# UNO-TH_Rev3e_Eagle.net
KiCad netlist of a schematic drawn in EAGLE
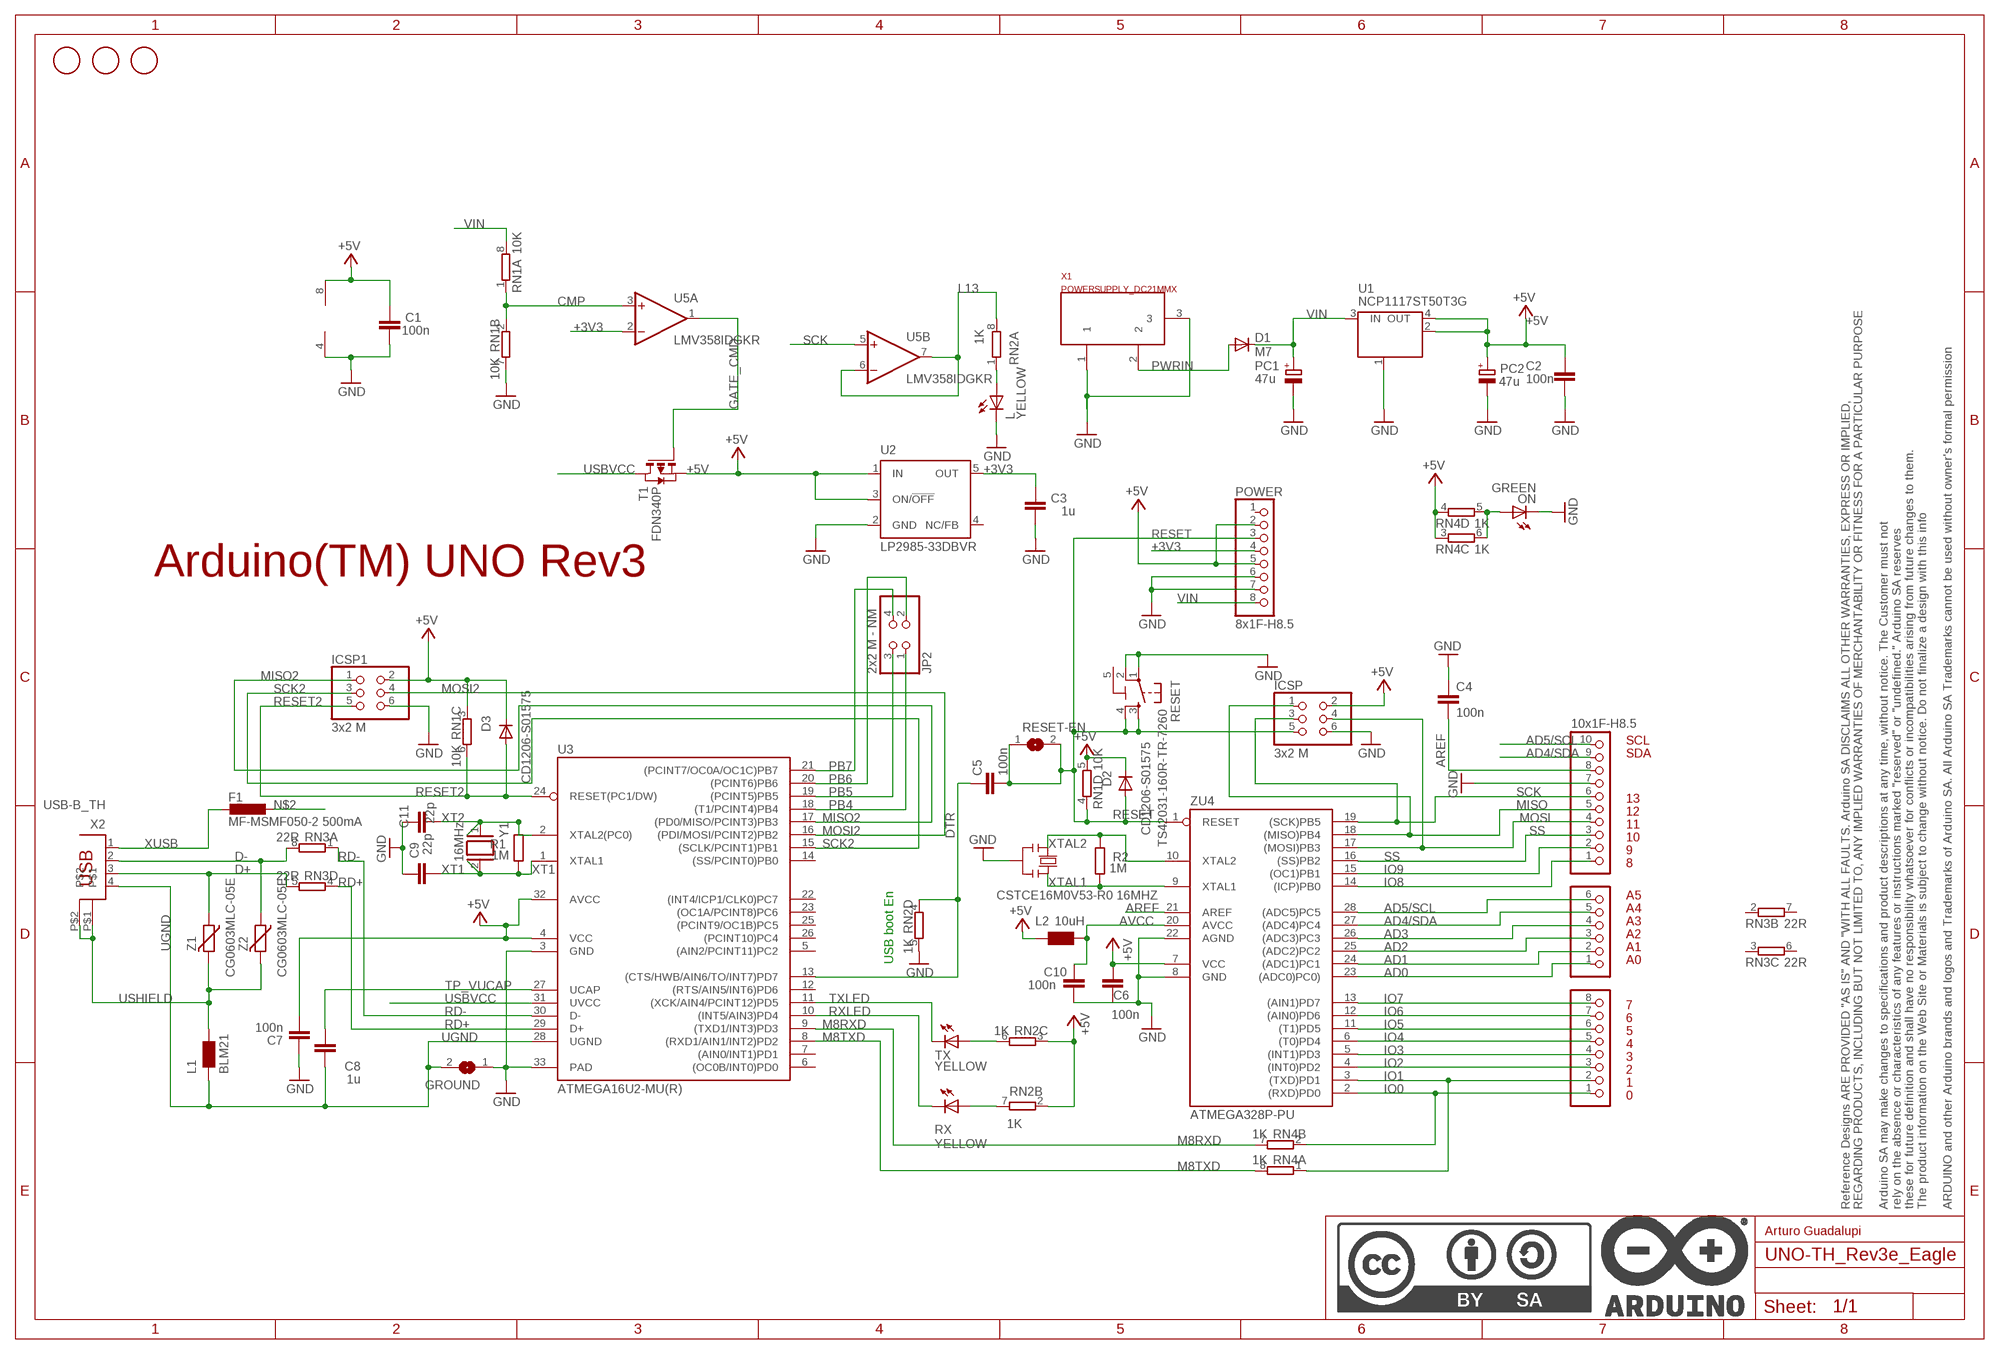
[diagram p0: schematic, sheet 1]

(export (version "E")
  (design (tool "Eeschema 10.0.6"))
  (components
    (comp (ref "AD")
      (value "6x1F-H8.5")
      (footprint "eagle-import:1X06")
      (libsource (lib "eagle-import") (part "PINHD-1X6"))
    )
    (comp (ref "C1")
      (value "100n")
      (footprint "eagle-import:C0603-ROUND")
      (libsource (lib "eagle-import") (part "C-EU0603-RND"))
    )
    (comp (ref "C2")
      (value "100n")
      (footprint "eagle-import:C0603-ROUND")
      (libsource (lib "eagle-import") (part "C-EU0603-RND"))
    )
    (comp (ref "C3")
      (value "1u")
      (footprint "eagle-import:C0603-ROUND")
      (libsource (lib "eagle-import") (part "C-EU0603-RND"))
    )
    (comp (ref "C4")
      (value "100n")
      (footprint "eagle-import:C0603-ROUND")
      (libsource (lib "eagle-import") (part "C-EU0603-RND"))
    )
    (comp (ref "C5")
      (value "100n")
      (footprint "eagle-import:C0603-ROUND")
      (libsource (lib "eagle-import") (part "C-EU0603-RND"))
    )
    (comp (ref "C6")
      (value "100n")
      (footprint "eagle-import:C0603-ROUND")
      (libsource (lib "eagle-import") (part "C-EU0603-RND"))
    )
    (comp (ref "C7")
      (value "100n")
      (footprint "eagle-import:C0603-ROUND")
      (libsource (lib "eagle-import") (part "C-EU0603-RND"))
    )
    (comp (ref "C8")
      (value "1u")
      (footprint "eagle-import:C0603-ROUND")
      (libsource (lib "eagle-import") (part "C-EU0603-RND"))
    )
    (comp (ref "C9")
      (value "22p")
      (footprint "eagle-import:C0603-ROUND")
      (libsource (lib "eagle-import") (part "C-EU0603-RND"))
    )
    (comp (ref "C10")
      (value "100n")
      (footprint "eagle-import:C0603-ROUND")
      (libsource (lib "eagle-import") (part "C-EU0603-RND"))
    )
    (comp (ref "C11")
      (value "22p")
      (footprint "eagle-import:C0603-ROUND")
      (libsource (lib "eagle-import") (part "C-EU0603-RND"))
    )
    (comp (ref "D1")
      (value "M7")
      (footprint "eagle-import:SMB")
      (libsource (lib "eagle-import") (part "DIODE-SMB"))
    )
    (comp (ref "D2")
      (value "CD1206-S01575")
      (footprint "eagle-import:MINIMELF")
      (libsource (lib "eagle-import") (part "DIODE-MINIMELF"))
    )
    (comp (ref "D3")
      (value "CD1206-S01575")
      (footprint "eagle-import:MINIMELF")
      (libsource (lib "eagle-import") (part "DIODE-MINIMELF"))
    )
    (comp (ref "F1")
      (value "MF-MSMF050-2 500mA")
      (footprint "eagle-import:L1812")
      (libsource (lib "eagle-import") (part "L-EUL1812"))
    )
    (comp (ref "FD1")
      (value "FIDUCIALMOUNT")
      (footprint "eagle-import:FIDUCIA-MOUNT")
      (libsource (lib "eagle-import") (part "FIDUCIALMOUNT"))
    )
    (comp (ref "FD2")
      (value "FIDUCIALMOUNT")
      (footprint "eagle-import:FIDUCIA-MOUNT")
      (libsource (lib "eagle-import") (part "FIDUCIALMOUNT"))
    )
    (comp (ref "FD3")
      (value "FIDUCIALMOUNT")
      (footprint "eagle-import:FIDUCIA-MOUNT")
      (libsource (lib "eagle-import") (part "FIDUCIALMOUNT"))
    )
    (comp (ref "FRAME1")
      (value "DNP")
      (footprint "eagle-import:FRAME")
      (libsource (lib "eagle-import") (part "A3-FRAME"))
    )
    (comp (ref "GROUND")
      (value "SJ")
      (footprint "eagle-import:SJ")
      (libsource (lib "eagle-import") (part "SJ"))
    )
    (comp (ref "ICSP")
      (value "3x2 M")
      (footprint "eagle-import:2X03")
      (libsource (lib "eagle-import") (part "PINHD-2X3"))
    )
    (comp (ref "ICSP1")
      (value "3x2 M")
      (footprint "eagle-import:2X03")
      (libsource (lib "eagle-import") (part "PINHD-2X3"))
    )
    (comp (ref "IOH")
      (value "10x1F-H8.5")
      (footprint "eagle-import:1X10")
      (libsource (lib "eagle-import") (part "PINHD-1X10_ARD"))
    )
    (comp (ref "IOL")
      (value "8x1F-H8.5")
      (footprint "eagle-import:1X08")
      (libsource (lib "eagle-import") (part "PINHD-1X8"))
    )
    (comp (ref "JP2")
      (value "2x2 M - NM")
      (footprint "eagle-import:2X02")
      (libsource (lib "eagle-import") (part "PINHD-2X2"))
    )
    (comp (ref "L")
      (value "YELLOW")
      (footprint "eagle-import:CHIP-LED0805")
      (libsource (lib "eagle-import") (part "LEDCHIP-LED0805"))
    )
    (comp (ref "L1")
      (value "BLM21")
      (footprint "eagle-import:0805")
      (libsource (lib "eagle-import") (part "WE-CBF_0805"))
    )
    (comp (ref "L2")
      (value "10uH")
      (footprint "eagle-import:0805")
      (fields (field (name "PART_NUMBER") "CV201210-100K"))
      (libsource (lib "eagle-import") (part "0715_CV201210-100K"))
    )
    (comp (ref "ON")
      (value "GREEN")
      (footprint "eagle-import:CHIP-LED0805")
      (libsource (lib "eagle-import") (part "LEDCHIP-LED0805"))
    )
    (comp (ref "PC1")
      (value "47u")
      (footprint "eagle-import:PANASONIC_D")
      (libsource (lib "eagle-import") (part "CPOL-EUD"))
    )
    (comp (ref "PC2")
      (value "47u")
      (footprint "eagle-import:PANASONIC_D")
      (libsource (lib "eagle-import") (part "CPOL-EUD"))
    )
    (comp (ref "POWER")
      (value "8x1F-H8.5")
      (footprint "eagle-import:1X08")
      (libsource (lib "eagle-import") (part "PINHD-1X8"))
    )
    (comp (ref "R1")
      (value "1M")
      (footprint "eagle-import:R0603-ROUND")
      (libsource (lib "eagle-import") (part "R-EU_R0603"))
    )
    (comp (ref "R2")
      (value "1M")
      (footprint "eagle-import:R0603-ROUND")
      (libsource (lib "eagle-import") (part "R-EU_R0603"))
    )
    (comp (ref "RESET")
      (value "TS42031-160R-TR-7260")
      (footprint "eagle-import:TS42")
      (libsource (lib "eagle-import") (part "TS42"))
    )
    (comp (ref "RESET-EN")
      (value "SJ")
      (footprint "eagle-import:SJ")
      (libsource (lib "eagle-import") (part "SJ"))
    )
    (comp (ref "RN1")
      (value "10K")
      (footprint "eagle-import:CAY16")
      (libsource (lib "eagle-import") (part "4R-NCAY16"))
    )
    (comp (ref "RN2")
      (value "1K")
      (footprint "eagle-import:CAY16")
      (libsource (lib "eagle-import") (part "4R-NCAY16"))
    )
    (comp (ref "RN3")
      (value "22R")
      (footprint "eagle-import:CAY16")
      (libsource (lib "eagle-import") (part "4R-NCAY16"))
    )
    (comp (ref "RN4")
      (value "1K")
      (footprint "eagle-import:CAY16")
      (libsource (lib "eagle-import") (part "4R-NCAY16"))
    )
    (comp (ref "RX")
      (value "YELLOW")
      (footprint "eagle-import:CHIP-LED0805")
      (libsource (lib "eagle-import") (part "LEDCHIP-LED0805"))
    )
    (comp (ref "T1")
      (value "FDN340P")
      (footprint "eagle-import:SOT-23")
      (libsource (lib "eagle-import") (part "PMOSSOT23"))
    )
    (comp (ref "TX")
      (value "YELLOW")
      (footprint "eagle-import:CHIP-LED0805")
      (libsource (lib "eagle-import") (part "LEDCHIP-LED0805"))
    )
    (comp (ref "U1")
      (value "NCP1117ST50T3G")
      (footprint "eagle-import:SOT223")
      (libsource (lib "eagle-import") (part "MC33269ST-3.3T3"))
    )
    (comp (ref "U2")
      (value "LP2985-33DBVR")
      (footprint "eagle-import:SOT23-DBV")
      (libsource (lib "eagle-import") (part "LP2985-XXDBVR33"))
    )
    (comp (ref "U3")
      (value "ATMEGA16U2-MU(R)")
      (footprint "eagle-import:MLF32")
      (libsource (lib "eagle-import") (part "ATMEGA16U2-MU"))
    )
    (comp (ref "U5")
      (value "LMV358IDGKR")
      (footprint "eagle-import:MSOP08")
      (libsource (lib "eagle-import") (part "LMV358?MMX"))
    )
    (comp (ref "X1")
      (value "POWERSUPPLY_DC21MMX")
      (footprint "eagle-import:POWERSUPPLY_DC-21MM")
      (libsource (lib "eagle-import") (part "POWERSUPPLY_DC21MMX"))
    )
    (comp (ref "X2")
      (value "USB-B_TH")
      (footprint "eagle-import:PN61729")
      (libsource (lib "eagle-import") (part "PN61729"))
    )
    (comp (ref "Y1")
      (value "16MHz")
      (footprint "eagle-import:QS")
      (libsource (lib "eagle-import") (part "XTAL/S"))
    )
    (comp (ref "Y2")
      (value "CSTCE16M0V53-R0 16MHZ")
      (footprint "eagle-import:RESONATOR")
      (libsource (lib "eagle-import") (part "RESONATORMU"))
    )
    (comp (ref "Z1")
      (value "CG0603MLC-05E")
      (footprint "eagle-import:CT_CN0603")
      (libsource (lib "eagle-import") (part "VARISTORCN0603"))
    )
    (comp (ref "Z2")
      (value "CG0603MLC-05E")
      (footprint "eagle-import:CT_CN0603")
      (libsource (lib "eagle-import") (part "VARISTORCN0603"))
    )
    (comp (ref "ZU4")
      (value "ATMEGA328P-PU")
      (footprint "eagle-import:DIL28-3")
      (libsource (lib "eagle-import") (part "ATMEGA328P-PU"))
    )
  )
  (nets
    (net (code "1") (name "+5V") (class "Default")
      (node (ref "C1") (pin "2") (pinfunction "2_2") (pintype "passive"))
      (node (ref "C2") (pin "2") (pinfunction "2_2") (pintype "passive"))
      (node (ref "C6") (pin "2") (pinfunction "2_2") (pintype "passive"))
      (node (ref "C7") (pin "1") (pinfunction "1_1") (pintype "passive"))
      (node (ref "D2") (pin "C") (pinfunction "C_C") (pintype "passive"))
      (node (ref "D3") (pin "C") (pinfunction "C_C") (pintype "passive"))
      (node (ref "ICSP") (pin "2") (pinfunction "2_2") (pintype "passive"))
      (node (ref "ICSP1") (pin "2") (pinfunction "2_2") (pintype "passive"))
      (node (ref "L2") (pin "1") (pinfunction "1_1") (pintype "passive"))
      (node (ref "PC2") (pin "+") (pinfunction "+_+") (pintype "passive"))
      (node (ref "POWER") (pin "2") (pinfunction "2_2") (pintype "passive"))
      (node (ref "POWER") (pin "5") (pinfunction "5_5") (pintype "passive"))
      (node (ref "RN1") (pin "3") (pinfunction "1_3") (pintype "passive"))
      (node (ref "RN1") (pin "5") (pinfunction "2_5") (pintype "passive"))
      (node (ref "RN2") (pin "2") (pinfunction "1_2") (pintype "passive"))
      (node (ref "RN2") (pin "3") (pinfunction "1_3") (pintype "passive"))
      (node (ref "RN4") (pin "3") (pinfunction "1_3") (pintype "passive"))
      (node (ref "RN4") (pin "4") (pinfunction "1_4") (pintype "passive"))
      (node (ref "T1") (pin "2") (pinfunction "S_2") (pintype "passive"))
      (node (ref "U1") (pin "2") (pinfunction "OUT_2") (pintype "passive"))
      (node (ref "U1") (pin "4") (pinfunction "OUT_4") (pintype "passive"))
      (node (ref "U2") (pin "1") (pinfunction "IN_1") (pintype "input"))
      (node (ref "U2") (pin "3") (pinfunction "ON/~{OFF}_3") (pintype "input"))
      (node (ref "U3") (pin "32") (pinfunction "AVCC_32") (pintype "power_in"))
      (node (ref "U3") (pin "4") (pinfunction "VCC_4") (pintype "power_in"))
      (node (ref "U5") (pin "8") (pinfunction "V+_8") (pintype "power_in"))
      (node (ref "ZU4") (pin "7") (pinfunction "VCC_7") (pintype "power_in"))
    )
    (net (code "2") (name "/+3V3") (class "Default")
      (node (ref "C3") (pin "2") (pinfunction "2_2") (pintype "passive"))
      (node (ref "POWER") (pin "4") (pinfunction "4_4") (pintype "passive"))
      (node (ref "U2") (pin "5") (pinfunction "OUT_5") (pintype "passive"))
      (node (ref "U5") (pin "2") (pinfunction "-IN_2") (pintype "input"))
    )
    (net (code "3") (name "/5-GND") (class "Default")
      (node (ref "RESET") (pin "5") (pinfunction "5-GND_5") (pintype "power_in"))
    )
    (net (code "4") (name "/AD0") (class "Default")
      (node (ref "AD") (pin "1") (pinfunction "1_1") (pintype "passive"))
      (node (ref "ZU4") (pin "23") (pinfunction "(ADC0)PC0)_23") (pintype "bidirectional"))
    )
    (net (code "5") (name "/AD1") (class "Default")
      (node (ref "AD") (pin "2") (pinfunction "2_2") (pintype "passive"))
      (node (ref "ZU4") (pin "24") (pinfunction "(ADC1)PC1_24") (pintype "bidirectional"))
    )
    (net (code "6") (name "/AD2") (class "Default")
      (node (ref "AD") (pin "3") (pinfunction "3_3") (pintype "passive"))
      (node (ref "ZU4") (pin "25") (pinfunction "(ADC2)PC2_25") (pintype "bidirectional"))
    )
    (net (code "7") (name "/AD3") (class "Default")
      (node (ref "AD") (pin "4") (pinfunction "4_4") (pintype "passive"))
      (node (ref "ZU4") (pin "26") (pinfunction "(ADC3)PC3_26") (pintype "bidirectional"))
    )
    (net (code "8") (name "/AD4{slash}SDA") (class "Default")
      (node (ref "AD") (pin "5") (pinfunction "5_5") (pintype "passive"))
      (node (ref "IOH") (pin "9") (pinfunction "9_9") (pintype "passive"))
      (node (ref "ZU4") (pin "27") (pinfunction "(ADC4)PC4_27") (pintype "bidirectional"))
    )
    (net (code "9") (name "/AD5{slash}SCL") (class "Default")
      (node (ref "AD") (pin "6") (pinfunction "6_6") (pintype "passive"))
      (node (ref "IOH") (pin "10") (pinfunction "10_10") (pintype "passive"))
      (node (ref "ZU4") (pin "28") (pinfunction "(ADC5)PC5_28") (pintype "bidirectional"))
    )
    (net (code "10") (name "/AREF") (class "Default")
      (node (ref "C4") (pin "2") (pinfunction "2_2") (pintype "passive"))
      (node (ref "IOH") (pin "8") (pinfunction "8_8") (pintype "passive"))
      (node (ref "ZU4") (pin "21") (pinfunction "AREF_21") (pintype "passive"))
    )
    (net (code "11") (name "/AVCC") (class "Default")
      (node (ref "C10") (pin "2") (pinfunction "2_2") (pintype "passive"))
      (node (ref "L2") (pin "2") (pinfunction "2_2") (pintype "passive"))
      (node (ref "ZU4") (pin "20") (pinfunction "AVCC_20") (pintype "power_in"))
    )
    (net (code "12") (name "/CMP") (class "Default")
      (node (ref "RN1") (pin "1") (pinfunction "1_1") (pintype "passive"))
      (node (ref "RN1") (pin "2") (pinfunction "1_2") (pintype "passive"))
      (node (ref "U5") (pin "3") (pinfunction "+IN_3") (pintype "input"))
    )
    (net (code "13") (name "/D+") (class "Default")
      (node (ref "RN3") (pin "5") (pinfunction "2_5") (pintype "passive"))
      (node (ref "X2") (pin "3") (pinfunction "3_3") (pintype "bidirectional"))
      (node (ref "Z1") (pin "1") (pinfunction "1_1") (pintype "passive"))
    )
    (net (code "14") (name "/D-") (class "Default")
      (node (ref "RN3") (pin "8") (pinfunction "2_8") (pintype "passive"))
      (node (ref "X2") (pin "2") (pinfunction "2_2") (pintype "bidirectional"))
      (node (ref "Z2") (pin "1") (pinfunction "1_1") (pintype "passive"))
    )
    (net (code "15") (name "/DTR") (class "Default")
      (node (ref "C5") (pin "1") (pinfunction "1_1") (pintype "passive"))
      (node (ref "RN2") (pin "4") (pinfunction "1_4") (pintype "passive"))
      (node (ref "U3") (pin "13") (pinfunction "(CTS/HWB/AIN6/TO/INT7)PD7_13") (pintype "bidirectional"))
    )
    (net (code "16") (name "/GATE_CMD") (class "Default")
      (node (ref "T1") (pin "3") (pinfunction "G_3") (pintype "passive"))
      (node (ref "U5") (pin "1") (pinfunction "OUT_1") (pintype "output"))
    )
    (net (code "17") (name "/IO0") (class "Default")
      (node (ref "IOL") (pin "1") (pinfunction "1_1") (pintype "passive"))
      (node (ref "RN4") (pin "2") (pinfunction "1_2") (pintype "passive"))
      (node (ref "ZU4") (pin "2") (pinfunction "(RXD)PD0_2") (pintype "bidirectional"))
    )
    (net (code "18") (name "/IO1") (class "Default")
      (node (ref "IOL") (pin "2") (pinfunction "2_2") (pintype "passive"))
      (node (ref "RN4") (pin "1") (pinfunction "1_1") (pintype "passive"))
      (node (ref "ZU4") (pin "3") (pinfunction "(TXD)PD1_3") (pintype "bidirectional"))
    )
    (net (code "19") (name "/IO2") (class "Default")
      (node (ref "IOL") (pin "3") (pinfunction "3_3") (pintype "passive"))
      (node (ref "ZU4") (pin "4") (pinfunction "(INT0)PD2_4") (pintype "bidirectional"))
    )
    (net (code "20") (name "/IO3") (class "Default")
      (node (ref "IOL") (pin "4") (pinfunction "4_4") (pintype "passive"))
      (node (ref "ZU4") (pin "5") (pinfunction "(INT1)PD3_5") (pintype "bidirectional"))
    )
    (net (code "21") (name "/IO4") (class "Default")
      (node (ref "IOL") (pin "5") (pinfunction "5_5") (pintype "passive"))
      (node (ref "ZU4") (pin "6") (pinfunction "(T0)PD4_6") (pintype "bidirectional"))
    )
    (net (code "22") (name "/IO5") (class "Default")
      (node (ref "IOL") (pin "6") (pinfunction "6_6") (pintype "passive"))
      (node (ref "ZU4") (pin "11") (pinfunction "(T1)PD5_11") (pintype "bidirectional"))
    )
    (net (code "23") (name "/IO6") (class "Default")
      (node (ref "IOL") (pin "7") (pinfunction "7_7") (pintype "passive"))
      (node (ref "ZU4") (pin "12") (pinfunction "(AIN0)PD6_12") (pintype "bidirectional"))
    )
    (net (code "24") (name "/IO7") (class "Default")
      (node (ref "IOL") (pin "8") (pinfunction "8_8") (pintype "passive"))
      (node (ref "ZU4") (pin "13") (pinfunction "(AIN1)PD7_13") (pintype "bidirectional"))
    )
    (net (code "25") (name "/IO8") (class "Default")
      (node (ref "IOH") (pin "1") (pinfunction "1_1") (pintype "passive"))
      (node (ref "ZU4") (pin "14") (pinfunction "(ICP)PB0_14") (pintype "bidirectional"))
    )
    (net (code "26") (name "/IO9") (class "Default")
      (node (ref "IOH") (pin "2") (pinfunction "2_2") (pintype "passive"))
      (node (ref "ZU4") (pin "15") (pinfunction "(OC1)PB1_15") (pintype "bidirectional"))
    )
    (net (code "27") (name "/L13") (class "Default")
      (node (ref "RN2") (pin "8") (pinfunction "2_8") (pintype "passive"))
      (node (ref "U5") (pin "6") (pinfunction "-IN_6") (pintype "input"))
      (node (ref "U5") (pin "7") (pinfunction "OUT_7") (pintype "output"))
    )
    (net (code "28") (name "/M8RXD") (class "Default")
      (node (ref "RN4") (pin "7") (pinfunction "2_7") (pintype "passive"))
      (node (ref "U3") (pin "9") (pinfunction "(TXD1/INT3)PD3_9") (pintype "bidirectional"))
    )
    (net (code "29") (name "/M8TXD") (class "Default")
      (node (ref "RN4") (pin "8") (pinfunction "2_8") (pintype "passive"))
      (node (ref "U3") (pin "8") (pinfunction "(RXD1/AIN1/INT2)PD2_8") (pintype "bidirectional"))
    )
    (net (code "30") (name "/MISO") (class "Default")
      (node (ref "ICSP") (pin "1") (pinfunction "1_1") (pintype "passive"))
      (node (ref "IOH") (pin "5") (pinfunction "5_5") (pintype "passive"))
      (node (ref "ZU4") (pin "18") (pinfunction "(MISO)PB4_18") (pintype "bidirectional"))
    )
    (net (code "31") (name "/MISO2") (class "Default")
      (node (ref "ICSP1") (pin "1") (pinfunction "1_1") (pintype "passive"))
      (node (ref "U3") (pin "17") (pinfunction "(PD0/MISO/PCINT3)PB3_17") (pintype "bidirectional"))
    )
    (net (code "32") (name "/MOSI") (class "Default")
      (node (ref "ICSP") (pin "4") (pinfunction "4_4") (pintype "passive"))
      (node (ref "IOH") (pin "4") (pinfunction "4_4") (pintype "passive"))
      (node (ref "ZU4") (pin "17") (pinfunction "(MOSI)PB3_17") (pintype "bidirectional"))
    )
    (net (code "33") (name "/MOSI2") (class "Default")
      (node (ref "ICSP1") (pin "4") (pinfunction "4_4") (pintype "passive"))
      (node (ref "U3") (pin "16") (pinfunction "(PDI/MOSI/PCINT2)PB2_16") (pintype "bidirectional"))
    )
    (net (code "34") (name "/N$2") (class "Default")
      (node (ref "F1") (pin "1") (pinfunction "1_1") (pintype "passive"))
    )
    (net (code "35") (name "/PB4") (class "Default")
      (node (ref "JP2") (pin "1") (pinfunction "1_1") (pintype "passive"))
      (node (ref "U3") (pin "18") (pinfunction "(T1/PCINT4)PB4_18") (pintype "bidirectional"))
    )
    (net (code "36") (name "/PB5") (class "Default")
      (node (ref "JP2") (pin "3") (pinfunction "3_3") (pintype "passive"))
      (node (ref "U3") (pin "19") (pinfunction "(PCINT5)PB5_19") (pintype "bidirectional"))
    )
    (net (code "37") (name "/PB6") (class "Default")
      (node (ref "JP2") (pin "2") (pinfunction "2_2") (pintype "passive"))
      (node (ref "U3") (pin "20") (pinfunction "(PCINT6)PB6_20") (pintype "bidirectional"))
    )
    (net (code "38") (name "/PB7") (class "Default")
      (node (ref "JP2") (pin "4") (pinfunction "4_4") (pintype "passive"))
      (node (ref "U3") (pin "21") (pinfunction "(PCINT7/OC0A/OC1C)PB7_21") (pintype "bidirectional"))
    )
    (net (code "39") (name "/PWRIN") (class "Default")
      (node (ref "D1") (pin "A") (pinfunction "A_A") (pintype "passive"))
      (node (ref "X1") (pin "2") (pinfunction "2_2") (pintype "power_in"))
    )
    (net (code "40") (name "/RD+") (class "Default")
      (node (ref "RN3") (pin "4") (pinfunction "1_4") (pintype "passive"))
      (node (ref "U3") (pin "29") (pinfunction "D+_29") (pintype "bidirectional"))
    )
    (net (code "41") (name "/RD-") (class "Default")
      (node (ref "RN3") (pin "1") (pinfunction "1_1") (pintype "passive"))
      (node (ref "U3") (pin "30") (pinfunction "D-_30") (pintype "bidirectional"))
    )
    (net (code "42") (name "/RESET") (class "Default")
      (node (ref "C5") (pin "2") (pinfunction "2_2") (pintype "passive"))
      (node (ref "D2") (pin "A") (pinfunction "A_A") (pintype "passive"))
      (node (ref "ICSP") (pin "5") (pinfunction "5_5") (pintype "passive"))
      (node (ref "POWER") (pin "3") (pinfunction "3_3") (pintype "passive"))
      (node (ref "RESET") (pin "3") (pinfunction "3_3") (pintype "passive"))
      (node (ref "RESET") (pin "4") (pinfunction "4_4") (pintype "passive"))
      (node (ref "RESET-EN") (pin "1") (pinfunction "1_1") (pintype "passive"))
      (node (ref "RESET-EN") (pin "2") (pinfunction "2_2") (pintype "passive"))
      (node (ref "RN1") (pin "4") (pinfunction "1_4") (pintype "passive"))
      (node (ref "ZU4") (pin "1") (pinfunction "RESET_1") (pintype "input"))
    )
    (net (code "43") (name "/RESET2") (class "Default")
      (node (ref "D3") (pin "A") (pinfunction "A_A") (pintype "passive"))
      (node (ref "ICSP1") (pin "5") (pinfunction "5_5") (pintype "passive"))
      (node (ref "RN1") (pin "6") (pinfunction "2_6") (pintype "passive"))
      (node (ref "U3") (pin "24") (pinfunction "RESET(PC1/DW)_24") (pintype "input"))
    )
    (net (code "44") (name "/RXLED") (class "Default")
      (node (ref "RX") (pin "C") (pinfunction "C_C") (pintype "passive"))
      (node (ref "U3") (pin "10") (pinfunction "(INT5/AIN3)PD4_10") (pintype "bidirectional"))
    )
    (net (code "45") (name "/SCK") (class "Default")
      (node (ref "ICSP") (pin "3") (pinfunction "3_3") (pintype "passive"))
      (node (ref "IOH") (pin "6") (pinfunction "6_6") (pintype "passive"))
      (node (ref "U5") (pin "5") (pinfunction "+IN_5") (pintype "input"))
      (node (ref "ZU4") (pin "19") (pinfunction "(SCK)PB5_19") (pintype "bidirectional"))
    )
    (net (code "46") (name "/SCK2") (class "Default")
      (node (ref "ICSP1") (pin "3") (pinfunction "3_3") (pintype "passive"))
      (node (ref "U3") (pin "15") (pinfunction "(SCLK/PCINT1)PB1_15") (pintype "bidirectional"))
    )
    (net (code "47") (name "/SS") (class "Default")
      (node (ref "IOH") (pin "3") (pinfunction "3_3") (pintype "passive"))
      (node (ref "ZU4") (pin "16") (pinfunction "(SS)PB2_16") (pintype "bidirectional"))
    )
    (net (code "48") (name "/TP_VUCAP") (class "Default")
      (node (ref "C8") (pin "1") (pinfunction "1_1") (pintype "passive"))
      (node (ref "U3") (pin "27") (pinfunction "UCAP_27") (pintype "passive"))
    )
    (net (code "49") (name "/TXLED") (class "Default")
      (node (ref "TX") (pin "C") (pinfunction "C_C") (pintype "passive"))
      (node (ref "U3") (pin "11") (pinfunction "(XCK/AIN4/PCINT12)PD5_11") (pintype "bidirectional"))
    )
    (net (code "50") (name "/UGND") (class "Default")
      (node (ref "C8") (pin "2") (pinfunction "2_2") (pintype "passive"))
      (node (ref "GROUND") (pin "2") (pinfunction "2_2") (pintype "passive"))
      (node (ref "L1") (pin "1") (pinfunction "1_1") (pintype "passive"))
      (node (ref "U3") (pin "28") (pinfunction "UGND_28") (pintype "power_in"))
      (node (ref "X2") (pin "4") (pinfunction "4_4") (pintype "bidirectional"))
    )
    (net (code "51") (name "/USBVCC") (class "Default")
      (node (ref "T1") (pin "1") (pinfunction "D_1") (pintype "passive"))
      (node (ref "U3") (pin "31") (pinfunction "UVCC_31") (pintype "power_in"))
    )
    (net (code "52") (name "/USHIELD") (class "Default")
      (node (ref "L1") (pin "2") (pinfunction "2_2") (pintype "passive"))
      (node (ref "X2") (pin "P$1") (pinfunction "P$1_P$1") (pintype "bidirectional"))
      (node (ref "X2") (pin "P$2") (pinfunction "P$2_P$2") (pintype "bidirectional"))
      (node (ref "Z1") (pin "2") (pinfunction "2_2") (pintype "passive"))
      (node (ref "Z2") (pin "2") (pinfunction "2_2") (pintype "passive"))
    )
    (net (code "53") (name "/VIN") (class "Default")
      (node (ref "D1") (pin "C") (pinfunction "C_C") (pintype "passive"))
      (node (ref "PC1") (pin "+") (pinfunction "+_+") (pintype "passive"))
      (node (ref "POWER") (pin "8") (pinfunction "8_8") (pintype "passive"))
      (node (ref "RN1") (pin "8") (pinfunction "2_8") (pintype "passive"))
      (node (ref "U1") (pin "3") (pinfunction "IN_3") (pintype "input"))
    )
    (net (code "54") (name "/XT1") (class "Default")
      (node (ref "C9") (pin "1") (pinfunction "1_1") (pintype "passive"))
      (node (ref "R1") (pin "1") (pinfunction "1_1") (pintype "passive"))
      (node (ref "U3") (pin "1") (pinfunction "XTAL1_1") (pintype "bidirectional"))
      (node (ref "Y1") (pin "2") (pinfunction "2_2") (pintype "passive"))
    )
    (net (code "55") (name "/XT2") (class "Default")
      (node (ref "C11") (pin "1") (pinfunction "1_1") (pintype "passive"))
      (node (ref "R1") (pin "2") (pinfunction "2_2") (pintype "passive"))
      (node (ref "U3") (pin "2") (pinfunction "XTAL2(PC0)_2") (pintype "bidirectional"))
      (node (ref "Y1") (pin "1") (pinfunction "1_1") (pintype "passive"))
    )
    (net (code "56") (name "/XTAL1") (class "Default")
      (node (ref "R2") (pin "1") (pinfunction "1_1") (pintype "passive"))
      (node (ref "Y2") (pin "3") (pinfunction "3_3") (pintype "passive"))
      (node (ref "ZU4") (pin "9") (pinfunction "XTAL1_9") (pintype "bidirectional"))
    )
    (net (code "57") (name "/XTAL2") (class "Default")
      (node (ref "R2") (pin "2") (pinfunction "2_2") (pintype "passive"))
      (node (ref "Y2") (pin "1") (pinfunction "1_1") (pintype "passive"))
      (node (ref "ZU4") (pin "10") (pinfunction "XTAL2_10") (pintype "bidirectional"))
    )
    (net (code "58") (name "/XUSB") (class "Default")
      (node (ref "F1") (pin "2") (pinfunction "2_2") (pintype "passive"))
      (node (ref "X2") (pin "1") (pinfunction "1_1") (pintype "bidirectional"))
    )
    (net (code "59") (name "GND") (class "Default")
      (node (ref "C1") (pin "1") (pinfunction "1_1") (pintype "passive"))
      (node (ref "C10") (pin "1") (pinfunction "1_1") (pintype "passive"))
      (node (ref "C11") (pin "2") (pinfunction "2_2") (pintype "passive"))
      (node (ref "C2") (pin "1") (pinfunction "1_1") (pintype "passive"))
      (node (ref "C3") (pin "1") (pinfunction "1_1") (pintype "passive"))
      (node (ref "C4") (pin "1") (pinfunction "1_1") (pintype "passive"))
      (node (ref "C6") (pin "1") (pinfunction "1_1") (pintype "passive"))
      (node (ref "C7") (pin "2") (pinfunction "2_2") (pintype "passive"))
      (node (ref "C9") (pin "2") (pinfunction "2_2") (pintype "passive"))
      (node (ref "GROUND") (pin "1") (pinfunction "1_1") (pintype "passive"))
      (node (ref "ICSP") (pin "6") (pinfunction "6_6") (pintype "passive"))
      (node (ref "ICSP1") (pin "6") (pinfunction "6_6") (pintype "passive"))
      (node (ref "IOH") (pin "7") (pinfunction "7_7") (pintype "passive"))
      (node (ref "L") (pin "C") (pinfunction "C_C") (pintype "passive"))
      (node (ref "ON") (pin "C") (pinfunction "C_C") (pintype "passive"))
      (node (ref "PC1") (pin "-") (pinfunction "-_-") (pintype "passive"))
      (node (ref "PC2") (pin "-") (pinfunction "-_-") (pintype "passive"))
      (node (ref "POWER") (pin "6") (pinfunction "6_6") (pintype "passive"))
      (node (ref "POWER") (pin "7") (pinfunction "7_7") (pintype "passive"))
      (node (ref "RESET") (pin "1") (pinfunction "1_1") (pintype "passive"))
      (node (ref "RESET") (pin "2") (pinfunction "2_2") (pintype "passive"))
      (node (ref "RN1") (pin "7") (pinfunction "2_7") (pintype "passive"))
      (node (ref "RN2") (pin "5") (pinfunction "2_5") (pintype "passive"))
      (node (ref "U1") (pin "1") (pinfunction "GND/ADJ_1") (pintype "input"))
      (node (ref "U2") (pin "2") (pinfunction "GND_2") (pintype "power_in"))
      (node (ref "U3") (pin "3") (pinfunction "GND_3") (pintype "power_in"))
      (node (ref "U3") (pin "33") (pinfunction "PAD_33") (pintype "power_in"))
      (node (ref "U5") (pin "4") (pinfunction "V-_4") (pintype "power_in"))
      (node (ref "X1") (pin "1") (pinfunction "1_1") (pintype "power_in"))
      (node (ref "X1") (pin "3") (pinfunction "3_3") (pintype "power_in"))
      (node (ref "Y2") (pin "2") (pinfunction "2_2") (pintype "passive"))
      (node (ref "ZU4") (pin "22") (pinfunction "AGND_22") (pintype "power_in"))
      (node (ref "ZU4") (pin "8") (pinfunction "GND_8") (pintype "power_in"))
    )
    (net (code "60") (name "Net-(L-PadA)") (class "Default")
      (node (ref "L") (pin "A") (pinfunction "A_A") (pintype "passive"))
      (node (ref "RN2") (pin "1") (pinfunction "1_1") (pintype "passive"))
    )
    (net (code "61") (name "Net-(RN2B-2)") (class "Default")
      (node (ref "RN2") (pin "7") (pinfunction "2_7") (pintype "passive"))
      (node (ref "RX") (pin "A") (pinfunction "A_A") (pintype "passive"))
    )
    (net (code "62") (name "Net-(RN2C-2)") (class "Default")
      (node (ref "RN2") (pin "6") (pinfunction "2_6") (pintype "passive"))
      (node (ref "TX") (pin "A") (pinfunction "A_A") (pintype "passive"))
    )
    (net (code "63") (name "Net-(RN4C-2)") (class "Default")
      (node (ref "ON") (pin "A") (pinfunction "A_A") (pintype "passive"))
      (node (ref "RN4") (pin "5") (pinfunction "2_5") (pintype "passive"))
      (node (ref "RN4") (pin "6") (pinfunction "2_6") (pintype "passive"))
    )
    (net (code "64") (name "unconnected-(POWER-Pad1)") (class "Default")
      (node (ref "POWER") (pin "1") (pinfunction "1_1") (pintype "passive"))
    )
    (net (code "65") (name "unconnected-(RN3B-1-Pad2)") (class "Default")
      (node (ref "RN3") (pin "2") (pinfunction "1_2") (pintype "passive"))
    )
    (net (code "66") (name "unconnected-(RN3B-2-Pad7)") (class "Default")
      (node (ref "RN3") (pin "7") (pinfunction "2_7") (pintype "passive"))
    )
    (net (code "67") (name "unconnected-(RN3C-1-Pad3)") (class "Default")
      (node (ref "RN3") (pin "3") (pinfunction "1_3") (pintype "passive"))
    )
    (net (code "68") (name "unconnected-(RN3C-2-Pad6)") (class "Default")
      (node (ref "RN3") (pin "6") (pinfunction "2_6") (pintype "passive"))
    )
    (net (code "69") (name "unconnected-(U2-NC{slash}FB-Pad4)") (class "Default")
      (node (ref "U2") (pin "4") (pinfunction "NC/FB_4") (pintype "passive"))
    )
    (net (code "70") (name "unconnected-(U3-(AIN0{slash}INT1)PD1-Pad7)") (class "Default")
      (node (ref "U3") (pin "7") (pinfunction "(AIN0/INT1)PD1_7") (pintype "bidirectional"))
    )
    (net (code "71") (name "unconnected-(U3-(AIN2{slash}PCINT11)PC2-Pad5)") (class "Default")
      (node (ref "U3") (pin "5") (pinfunction "(AIN2/PCINT11)PC2_5") (pintype "bidirectional"))
    )
    (net (code "72") (name "unconnected-(U3-(INT4{slash}ICP1{slash}CLK0)PC7-Pad22)") (class "Default")
      (node (ref "U3") (pin "22") (pinfunction "(INT4/ICP1/CLK0)PC7_22") (pintype "bidirectional"))
    )
    (net (code "73") (name "unconnected-(U3-(OC0B{slash}INT0)PD0-Pad6)") (class "Default")
      (node (ref "U3") (pin "6") (pinfunction "(OC0B/INT0)PD0_6") (pintype "bidirectional"))
    )
    (net (code "74") (name "unconnected-(U3-(OC1A{slash}PCINT8)PC6-Pad23)") (class "Default")
      (node (ref "U3") (pin "23") (pinfunction "(OC1A/PCINT8)PC6_23") (pintype "bidirectional"))
    )
    (net (code "75") (name "unconnected-(U3-(PCINT9{slash}OC1B)PC5-Pad25)") (class "Default")
      (node (ref "U3") (pin "25") (pinfunction "(PCINT9/OC1B)PC5_25") (pintype "bidirectional"))
    )
    (net (code "76") (name "unconnected-(U3-(PCINT10)PC4-Pad26)") (class "Default")
      (node (ref "U3") (pin "26") (pinfunction "(PCINT10)PC4_26") (pintype "bidirectional"))
    )
    (net (code "77") (name "unconnected-(U3-(RTS{slash}AIN5{slash}INT6)PD6-Pad12)") (class "Default")
      (node (ref "U3") (pin "12") (pinfunction "(RTS/AIN5/INT6)PD6_12") (pintype "bidirectional"))
    )
    (net (code "78") (name "unconnected-(U3-(SS{slash}PCINT0)PB0-Pad14)") (class "Default")
      (node (ref "U3") (pin "14") (pinfunction "(SS/PCINT0)PB0_14") (pintype "bidirectional"))
    )
  )
)
